# DirCtl.net
KiCad netlist of a schematic drawn in Altium Designer
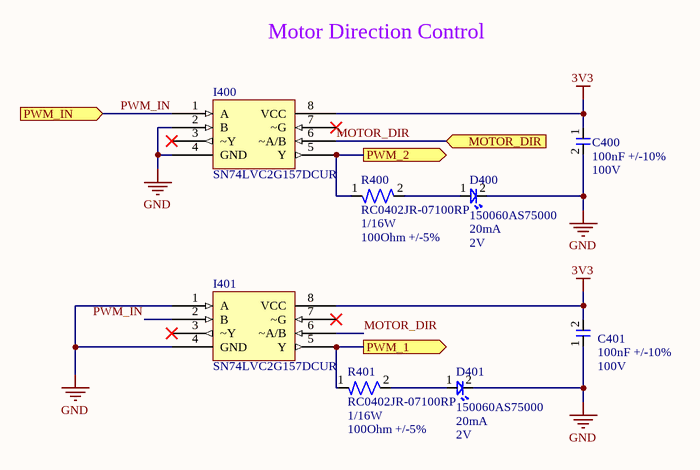
[diagram p0: DirCtl.SchDoc]

(export (version "E")
  (design (tool "Eeschema 10.0.6"))
  (components
    (comp (ref "C400")
      (value "CC0603KRX7R0BB104")
      (footprint "MasterLib:CAP-0603")
      (description "CAP CER 0.1UF 100V X7R 0603")
      (fields
        (field (name "MANUFACTURER") "YAGEO")
        (field (name "CAPACITANCE") "100nF +/-10%")
        (field (name "VOLTAGE RATING") "100V")
      )
      (libsource (lib "MasterLib") (part "CAP-100N-0001"))
    )
    (comp (ref "C401")
      (value "CC0603KRX7R0BB104")
      (footprint "MasterLib:CAP-0603")
      (description "CAP CER 0.1UF 100V X7R 0603")
      (fields
        (field (name "MANUFACTURER") "YAGEO")
        (field (name "CAPACITANCE") "100nF +/-10%")
        (field (name "VOLTAGE RATING") "100V")
      )
      (libsource (lib "MasterLib") (part "CAP-100N-0001"))
    )
    (comp (ref "D400")
      (value "150060AS75000")
      (footprint "MasterLib:LED-0603")
      (description "CAP CER 0.1UF 100V X7R 0603")
      (fields
        (field (name "MANUFACTURER") "Wurth Electronik")
        (field (name "CURRENT RATING") "20mA")
        (field (name "VF") "2V")
      )
      (libsource (lib "MasterLib") (part "LED_Amber_0001"))
    )
    (comp (ref "D401")
      (value "150060AS75000")
      (footprint "MasterLib:LED-0603")
      (description "CAP CER 0.1UF 100V X7R 0603")
      (fields
        (field (name "MANUFACTURER") "Wurth Electronik")
        (field (name "CURRENT RATING") "20mA")
        (field (name "VF") "2V")
      )
      (libsource (lib "MasterLib") (part "LED_Amber_0001"))
    )
    (comp (ref "I400")
      (value "SN74LVC2G157DCUR")
      (footprint "MasterLib:IC-MUX-8VSSOP")
      (libsource (lib "MasterLib") (part "IC-MUX-0001"))
    )
    (comp (ref "I401")
      (value "SN74LVC2G157DCUR")
      (footprint "MasterLib:IC-MUX-8VSSOP")
      (description "Multiplexer 1 x 2:1 8-VSSOP")
      (libsource (lib "MasterLib") (part "IC-MUX-0001"))
    )
    (comp (ref "R400")
      (value "RC0402JR-07100RP")
      (footprint "MasterLib:RES-0402")
      (description "RES SMD 100 OHM 5% 1/16W 0402")
      (fields
        (field (name "MANUFACTURER") "YAGEO")
        (field (name "POWER RATING") "1/16W")
        (field (name "RESISTANCE") "100Ohm +/-5%")
      )
      (libsource (lib "MasterLib") (part "RES-100-0001"))
    )
    (comp (ref "R401")
      (value "RC0402JR-07100RP")
      (footprint "MasterLib:RES-0402")
      (description "RES SMD 100 OHM 5% 1/16W 0402")
      (fields
        (field (name "MANUFACTURER") "YAGEO")
        (field (name "POWER RATING") "1/16W")
        (field (name "RESISTANCE") "100Ohm +/-5%")
      )
      (libsource (lib "MasterLib") (part "RES-100-0001"))
    )
  )
  (nets
    (net (code "1") (name "/MOTOR_DIR") (class "Default")
      (node (ref "I400") (pin "6") (pinfunction "~A/B_6") (pintype "input"))
      (node (ref "I401") (pin "6") (pinfunction "~A/B_6") (pintype "input"))
    )
    (net (code "2") (name "/PWM_1") (class "Default")
      (node (ref "I401") (pin "5") (pinfunction "Y_5") (pintype "output"))
      (node (ref "R401") (pin "1") (pinfunction "1_1") (pintype "passive"))
    )
    (net (code "3") (name "/PWM_2") (class "Default")
      (node (ref "I400") (pin "5") (pinfunction "Y_5") (pintype "output"))
      (node (ref "R400") (pin "1") (pinfunction "1_1") (pintype "passive"))
    )
    (net (code "4") (name "/PWM_IN") (class "Default")
      (node (ref "I400") (pin "1") (pinfunction "A_1") (pintype "input"))
      (node (ref "I401") (pin "2") (pinfunction "B_2") (pintype "input"))
    )
    (net (code "5") (name "3V3") (class "Default")
      (node (ref "C400") (pin "1") (pinfunction "1_1") (pintype "passive"))
      (node (ref "C401") (pin "2") (pinfunction "2_2") (pintype "passive"))
      (node (ref "I400") (pin "8") (pinfunction "VCC_8") (pintype "power_in"))
      (node (ref "I401") (pin "8") (pinfunction "VCC_8") (pintype "power_in"))
    )
    (net (code "6") (name "GND") (class "Default")
      (node (ref "C400") (pin "2") (pinfunction "2_2") (pintype "passive"))
      (node (ref "C401") (pin "1") (pinfunction "1_1") (pintype "passive"))
      (node (ref "D400") (pin "2") (pinfunction "2_2") (pintype "passive"))
      (node (ref "D401") (pin "2") (pinfunction "2_2") (pintype "passive"))
      (node (ref "I400") (pin "2") (pinfunction "B_2") (pintype "input"))
      (node (ref "I400") (pin "4") (pinfunction "GND_4") (pintype "power_in"))
      (node (ref "I401") (pin "1") (pinfunction "A_1") (pintype "input"))
      (node (ref "I401") (pin "4") (pinfunction "GND_4") (pintype "power_in"))
    )
    (net (code "7") (name "Net-(D400-Pad1)") (class "Default")
      (node (ref "D400") (pin "1") (pinfunction "1_1") (pintype "passive"))
      (node (ref "R400") (pin "2") (pinfunction "2_2") (pintype "passive"))
    )
    (net (code "8") (name "Net-(D401-Pad1)") (class "Default")
      (node (ref "D401") (pin "1") (pinfunction "1_1") (pintype "passive"))
      (node (ref "R401") (pin "2") (pinfunction "2_2") (pintype "passive"))
    )
    (net (code "9") (name "unconnected-(I400-~G-Pad7)") (class "Default")
      (node (ref "I400") (pin "7") (pinfunction "~G_7") (pintype "input+no_connect"))
    )
    (net (code "10") (name "unconnected-(I400-~Y-Pad3)") (class "Default")
      (node (ref "I400") (pin "3") (pinfunction "~Y_3") (pintype "output+no_connect"))
    )
    (net (code "11") (name "unconnected-(I401-~G-Pad7)") (class "Default")
      (node (ref "I401") (pin "7") (pinfunction "~G_7") (pintype "input+no_connect"))
    )
    (net (code "12") (name "unconnected-(I401-~Y-Pad3)") (class "Default")
      (node (ref "I401") (pin "3") (pinfunction "~Y_3") (pintype "output+no_connect"))
    )
  )
)
